# power.net
KiCad netlist of a schematic drawn in Altium Designer
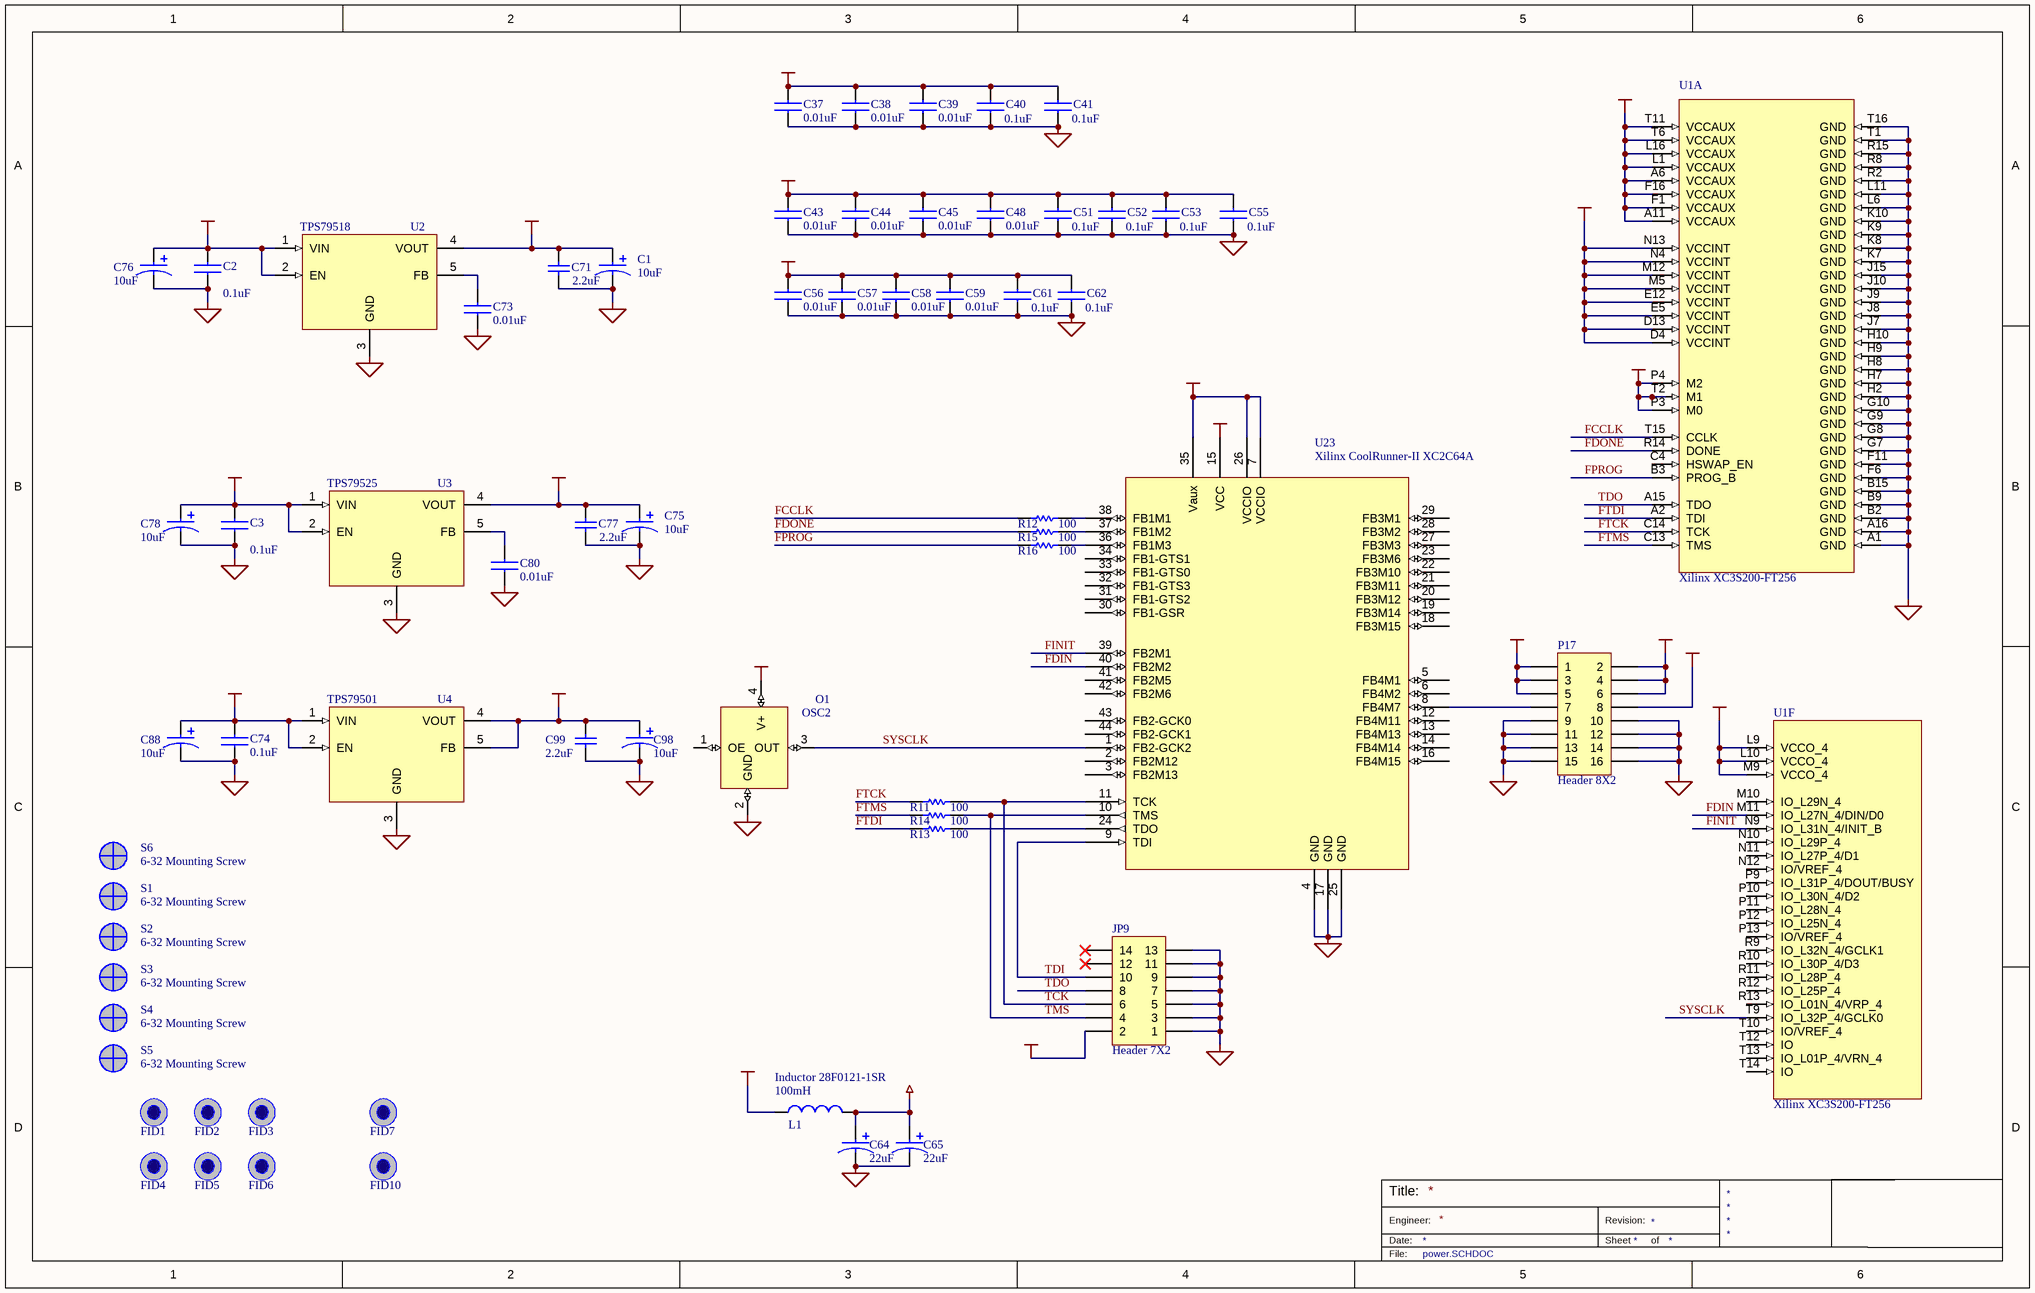
[diagram p0: power.SCHDOC]

(export (version "E")
  (design (tool "Eeschema 10.0.6"))
  (components
    (comp (ref "C1")
      (value "10uF")
      (footprint "6032")
      (description "Standard Capacitor")
      (fields (field (name "Comment") "POLCAP2"))
      (libsource (lib "parts") (part "POLCAP2"))
    )
    (comp (ref "C2")
      (value "0.1uF")
      (footprint "0603")
      (description "Standard Capacitor")
      (fields (field (name "Comment") "CAPACITOR"))
      (libsource (lib "parts") (part "CAPACITOR"))
    )
    (comp (ref "C3")
      (value "0.1uF")
      (footprint "0603")
      (description "Standard Capacitor")
      (fields (field (name "Comment") "CAPACITOR"))
      (libsource (lib "parts") (part "CAPACITOR"))
    )
    (comp (ref "C37")
      (value "0.01uF")
      (footprint "0402")
      (description "Standard Capacitor")
      (fields (field (name "Comment") "CAPACITOR"))
      (libsource (lib "parts") (part "CAPACITOR"))
    )
    (comp (ref "C38")
      (value "0.01uF")
      (footprint "0402")
      (description "Standard Capacitor")
      (fields (field (name "Comment") "CAPACITOR"))
      (libsource (lib "parts") (part "CAPACITOR"))
    )
    (comp (ref "C39")
      (value "0.01uF")
      (footprint "0402")
      (description "Standard Capacitor")
      (fields (field (name "Comment") "CAPACITOR"))
      (libsource (lib "parts") (part "CAPACITOR"))
    )
    (comp (ref "C40")
      (value "0.1uF")
      (footprint "0603")
      (description "Standard Capacitor")
      (fields (field (name "Comment") "CAPACITOR"))
      (libsource (lib "parts") (part "CAPACITOR"))
    )
    (comp (ref "C41")
      (value "0.1uF")
      (footprint "0603")
      (description "Standard Capacitor")
      (fields (field (name "Comment") "CAPACITOR"))
      (libsource (lib "parts") (part "CAPACITOR"))
    )
    (comp (ref "C43")
      (value "0.01uF")
      (footprint "0402")
      (description "Standard Capacitor")
      (fields (field (name "Comment") "CAPACITOR"))
      (libsource (lib "parts") (part "CAPACITOR"))
    )
    (comp (ref "C44")
      (value "0.01uF")
      (footprint "0402")
      (description "Standard Capacitor")
      (fields (field (name "Comment") "CAPACITOR"))
      (libsource (lib "parts") (part "CAPACITOR"))
    )
    (comp (ref "C45")
      (value "0.01uF")
      (footprint "0402")
      (description "Standard Capacitor")
      (fields (field (name "Comment") "CAPACITOR"))
      (libsource (lib "parts") (part "CAPACITOR"))
    )
    (comp (ref "C48")
      (value "0.01uF")
      (footprint "0402")
      (description "Standard Capacitor")
      (fields (field (name "Comment") "CAPACITOR"))
      (libsource (lib "parts") (part "CAPACITOR"))
    )
    (comp (ref "C51")
      (value "0.1uF")
      (footprint "0603")
      (description "Standard Capacitor")
      (fields (field (name "Comment") "CAPACITOR"))
      (libsource (lib "parts") (part "CAPACITOR"))
    )
    (comp (ref "C52")
      (value "0.1uF")
      (footprint "0603")
      (description "Standard Capacitor")
      (fields (field (name "Comment") "CAPACITOR"))
      (libsource (lib "parts") (part "CAPACITOR"))
    )
    (comp (ref "C53")
      (value "0.1uF")
      (footprint "0603")
      (description "Standard Capacitor")
      (fields (field (name "Comment") "CAPACITOR"))
      (libsource (lib "parts") (part "CAPACITOR"))
    )
    (comp (ref "C55")
      (value "0.1uF")
      (footprint "0603")
      (description "Standard Capacitor")
      (fields (field (name "Comment") "CAPACITOR"))
      (libsource (lib "parts") (part "CAPACITOR"))
    )
    (comp (ref "C56")
      (value "0.01uF")
      (footprint "0402")
      (description "Standard Capacitor")
      (fields (field (name "Comment") "CAPACITOR"))
      (libsource (lib "parts") (part "CAPACITOR"))
    )
    (comp (ref "C57")
      (value "0.01uF")
      (footprint "0402")
      (description "Standard Capacitor")
      (fields (field (name "Comment") "CAPACITOR"))
      (libsource (lib "parts") (part "CAPACITOR"))
    )
    (comp (ref "C58")
      (value "0.01uF")
      (footprint "0402")
      (description "Standard Capacitor")
      (fields (field (name "Comment") "CAPACITOR"))
      (libsource (lib "parts") (part "CAPACITOR"))
    )
    (comp (ref "C59")
      (value "0.01uF")
      (footprint "0402")
      (description "Standard Capacitor")
      (fields (field (name "Comment") "CAPACITOR"))
      (libsource (lib "parts") (part "CAPACITOR"))
    )
    (comp (ref "C61")
      (value "0.1uF")
      (footprint "0603")
      (description "Standard Capacitor")
      (fields (field (name "Comment") "CAPACITOR"))
      (libsource (lib "parts") (part "CAPACITOR"))
    )
    (comp (ref "C62")
      (value "0.1uF")
      (footprint "0603")
      (description "Standard Capacitor")
      (fields (field (name "Comment") "CAPACITOR"))
      (libsource (lib "parts") (part "CAPACITOR"))
    )
    (comp (ref "C64")
      (value "22uF")
      (footprint "6032")
      (description "Standard Capacitor")
      (fields (field (name "Comment") "POLCAP2"))
      (libsource (lib "parts") (part "POLCAP2"))
    )
    (comp (ref "C65")
      (value "22uF")
      (footprint "6032")
      (description "Standard Capacitor")
      (fields (field (name "Comment") "POLCAP2"))
      (libsource (lib "parts") (part "POLCAP2"))
    )
    (comp (ref "C71")
      (value "2.2uF")
      (footprint "1206")
      (description "Capacitor")
      (fields
        (field (name "MANUFACTURER") "Generic Components")
        (field (name "Comment") "Cap")
        (field (name "PUBLISHER") "Altium Limited")
      )
      (libsource (lib "Miscellaneous Devices") (part "Cap"))
    )
    (comp (ref "C73")
      (value "0.01uF")
      (footprint "0402")
      (description "Standard Capacitor")
      (fields (field (name "Comment") "CAPACITOR"))
      (libsource (lib "parts") (part "CAPACITOR"))
    )
    (comp (ref "C74")
      (value "0.1uF")
      (footprint "0603")
      (description "Standard Capacitor")
      (fields (field (name "Comment") "CAPACITOR"))
      (libsource (lib "parts") (part "CAPACITOR"))
    )
    (comp (ref "C75")
      (value "10uF")
      (footprint "6032")
      (description "Standard Capacitor")
      (fields (field (name "Comment") "POLCAP2"))
      (libsource (lib "parts") (part "POLCAP2"))
    )
    (comp (ref "C76")
      (value "10uF")
      (footprint "6032")
      (description "Standard Capacitor")
      (fields (field (name "Comment") "POLCAP2"))
      (libsource (lib "parts") (part "POLCAP2"))
    )
    (comp (ref "C77")
      (value "2.2uF")
      (footprint "1206")
      (description "Capacitor")
      (fields
        (field (name "MANUFACTURER") "Generic Components")
        (field (name "Comment") "Cap")
        (field (name "PUBLISHER") "Altium Limited")
      )
      (libsource (lib "Miscellaneous Devices") (part "Cap"))
    )
    (comp (ref "C78")
      (value "10uF")
      (footprint "6032")
      (description "Standard Capacitor")
      (fields (field (name "Comment") "POLCAP2"))
      (libsource (lib "parts") (part "POLCAP2"))
    )
    (comp (ref "C80")
      (value "0.01uF")
      (footprint "0402")
      (description "Standard Capacitor")
      (fields (field (name "Comment") "CAPACITOR"))
      (libsource (lib "parts") (part "CAPACITOR"))
    )
    (comp (ref "C88")
      (value "10uF")
      (footprint "6032")
      (description "Standard Capacitor")
      (fields (field (name "Comment") "POLCAP2"))
      (libsource (lib "parts") (part "POLCAP2"))
    )
    (comp (ref "C98")
      (value "10uF")
      (footprint "6032")
      (description "Standard Capacitor")
      (fields (field (name "Comment") "POLCAP2"))
      (libsource (lib "parts") (part "POLCAP2"))
    )
    (comp (ref "C99")
      (value "2.2uF")
      (footprint "1206")
      (description "Capacitor")
      (fields
        (field (name "MANUFACTURER") "Generic Components")
        (field (name "Comment") "Cap")
        (field (name "PUBLISHER") "Altium Limited")
      )
      (libsource (lib "Miscellaneous Devices") (part "Cap"))
    )
    (comp (ref "FID1")
      (value "FIDUCIAL")
      (footprint "FIDUCIAL")
      (description "Fiducial")
      (libsource (lib "parts") (part "FIDUCIAL"))
    )
    (comp (ref "FID2")
      (value "FIDUCIAL")
      (footprint "FIDUCIAL")
      (description "Fiducial")
      (libsource (lib "parts") (part "FIDUCIAL"))
    )
    (comp (ref "FID3")
      (value "FIDUCIAL")
      (footprint "FIDUCIAL")
      (description "Fiducial")
      (libsource (lib "parts") (part "FIDUCIAL"))
    )
    (comp (ref "FID4")
      (value "FIDUCIAL")
      (footprint "FIDUCIAL")
      (description "Fiducial")
      (libsource (lib "parts") (part "FIDUCIAL"))
    )
    (comp (ref "FID5")
      (value "FIDUCIAL")
      (footprint "FIDUCIAL")
      (description "Fiducial")
      (libsource (lib "parts") (part "FIDUCIAL"))
    )
    (comp (ref "FID6")
      (value "FIDUCIAL")
      (footprint "FIDUCIAL")
      (description "Fiducial")
      (libsource (lib "parts") (part "FIDUCIAL"))
    )
    (comp (ref "FID7")
      (value "FIDUCIAL")
      (footprint "FIDUCIAL")
      (description "Fiducial")
      (libsource (lib "parts") (part "FIDUCIAL"))
    )
    (comp (ref "FID10")
      (value "FIDUCIAL")
      (footprint "FIDUCIAL")
      (description "Fiducial")
      (libsource (lib "parts") (part "FIDUCIAL"))
    )
    (comp (ref "JP9")
      (value "Header 7X2")
      (footprint "SMT 2x7 2mm HDR")
      (description "Header, 7-Pin, Dual row")
      (fields (field (name "MANUFACTURER") "Generic Components") (field (name "PUBLISHER") "Altium Limited"))
      (libsource (lib "Miscellaneous Connectors") (part "Header 7X2"))
    )
    (comp (ref "L1")
      (value "Inductor 28F0121-1SR")
      (footprint "STEWARD_1SR")
      (description "Inductor")
      (fields
        (field (name "MANUFACTURER") "Generic Components")
        (field (name "ALTIUM_VALUE") "100mH")
        (field (name "PUBLISHER") "Altium Limited")
      )
      (libsource (lib "Miscellaneous Devices") (part "Inductor"))
    )
    (comp (ref "O1")
      (value "OSC2")
      (footprint "ECS-3953M")
      (description "ECS SMD Oscillator, ECS-3953M")
      (libsource (lib "parts") (part "OSC2"))
    )
    (comp (ref "P17")
      (value "Header 8X2")
      (footprint "MOLEX 15-91-2160")
      (description "Header, 8-Pin, Dual row")
      (fields (field (name "PUBLISHER") "Altium Limited"))
      (libsource (lib "Miscellaneous Connectors") (part "Header 8X2"))
    )
    (comp (ref "R11")
      (value "100")
      (footprint "0603")
      (description "Standard Passive Resistor")
      (fields (field (name "TOLERANCE") "1%") (field (name "Comment") "current-limiting series res"))
      (libsource (lib "parts") (part "RESISTOR"))
    )
    (comp (ref "R12")
      (value "100")
      (footprint "0603")
      (description "Standard Passive Resistor")
      (fields (field (name "TOLERANCE") "1%") (field (name "Comment") "current-limiting series res"))
      (libsource (lib "parts") (part "RESISTOR"))
    )
    (comp (ref "R13")
      (value "100")
      (footprint "0603")
      (description "Standard Passive Resistor")
      (fields (field (name "TOLERANCE") "1%") (field (name "Comment") "current-limiting series res"))
      (libsource (lib "parts") (part "RESISTOR"))
    )
    (comp (ref "R14")
      (value "100")
      (footprint "0603")
      (description "Standard Passive Resistor")
      (fields (field (name "TOLERANCE") "1%") (field (name "Comment") "current-limiting series res"))
      (libsource (lib "parts") (part "RESISTOR"))
    )
    (comp (ref "R15")
      (value "100")
      (footprint "0603")
      (description "Standard Passive Resistor")
      (fields (field (name "TOLERANCE") "1%") (field (name "Comment") "current-limiting series res"))
      (libsource (lib "parts") (part "RESISTOR"))
    )
    (comp (ref "R16")
      (value "100")
      (footprint "0603")
      (description "Standard Passive Resistor")
      (fields (field (name "TOLERANCE") "1%") (field (name "Comment") "current-limiting series res"))
      (libsource (lib "parts") (part "RESISTOR"))
    )
    (comp (ref "S1")
      (value "6-32 Mounting Screw")
      (footprint "SCREW6-32")
      (libsource (lib "parts") (part "MNTSCREW"))
    )
    (comp (ref "S2")
      (value "6-32 Mounting Screw")
      (footprint "SCREW6-32")
      (libsource (lib "parts") (part "MNTSCREW"))
    )
    (comp (ref "S3")
      (value "6-32 Mounting Screw")
      (footprint "SCREW6-32")
      (libsource (lib "parts") (part "MNTSCREW"))
    )
    (comp (ref "S4")
      (value "6-32 Mounting Screw")
      (footprint "SCREW6-32")
      (libsource (lib "parts") (part "MNTSCREW"))
    )
    (comp (ref "S5")
      (value "6-32 Mounting Screw")
      (footprint "SCREW6-32")
      (libsource (lib "parts") (part "MNTSCREW"))
    )
    (comp (ref "S6")
      (value "6-32 Mounting Screw")
      (footprint "SCREW6-32")
      (libsource (lib "parts") (part "MNTSCREW"))
    )
    (comp (ref "U1")
      (value "Xilinx XC3S200-FT256")
      (footprint "Xilinx FT256 BGA")
      (description "Xilinx Spartan-3 FPGA")
      (libsource (lib "parts") (part "XC3S200-FT256"))
    )
    (comp (ref "U2")
      (value "TPS79518")
      (footprint "SOT223-5/Simple")
      (description "TI Ultra-low-noise LDO")
      (libsource (lib "parts") (part "TPS795XX"))
    )
    (comp (ref "U3")
      (value "TPS79525")
      (footprint "SOT223-5/Simple")
      (description "TI Ultra-low-noise LDO")
      (libsource (lib "parts") (part "TPS795XX"))
    )
    (comp (ref "U4")
      (value "TPS79501")
      (footprint "SOT223-5/Simple")
      (description "TI Ultra-low-noise LDO")
      (libsource (lib "parts") (part "TPS795XX"))
    )
    (comp (ref "U23")
      (value "Xilinx CoolRunner-II XC2C64A")
      (footprint "QFP10x10-G44/G10N")
      (libsource (lib "parts") (part "XC2C64A-5VQ44C"))
    )
  )
  (nets
    (net (code "1") (name "+1.2VCC") (class "Default")
      (node (ref "C37") (pin "1") (pintype "passive"))
      (node (ref "C38") (pin "1") (pintype "passive"))
      (node (ref "C39") (pin "1") (pintype "passive"))
      (node (ref "C40") (pin "1") (pintype "passive"))
      (node (ref "C41") (pin "1") (pintype "passive"))
      (node (ref "C98") (pin "1") (pintype "passive"))
      (node (ref "C99") (pin "2") (pinfunction "2_2") (pintype "passive"))
      (node (ref "U1") (pin "D13") (pinfunction "VCCINT_D13") (pintype "input"))
      (node (ref "U1") (pin "D4") (pinfunction "VCCINT_D4") (pintype "input"))
      (node (ref "U1") (pin "E12") (pinfunction "VCCINT_E12") (pintype "input"))
      (node (ref "U1") (pin "E5") (pinfunction "VCCINT_E5") (pintype "input"))
      (node (ref "U1") (pin "M12") (pinfunction "VCCINT_M12") (pintype "input"))
      (node (ref "U1") (pin "M5") (pinfunction "VCCINT_M5") (pintype "input"))
      (node (ref "U1") (pin "N13") (pinfunction "VCCINT_N13") (pintype "input"))
      (node (ref "U1") (pin "N4") (pinfunction "VCCINT_N4") (pintype "input"))
      (node (ref "U4") (pin "4") (pinfunction "VOUT_4") (pintype "power_in"))
      (node (ref "U4") (pin "5") (pinfunction "FB_5") (pintype "passive"))
    )
    (net (code "2") (name "+1.8VCC") (class "Default")
      (node (ref "C1") (pin "1") (pintype "passive"))
      (node (ref "C71") (pin "2") (pinfunction "2_2") (pintype "passive"))
      (node (ref "U2") (pin "4") (pinfunction "VOUT_4") (pintype "power_in"))
      (node (ref "U23") (pin "15") (pinfunction "VCC_15") (pintype "power_in"))
    )
    (net (code "3") (name "+2.5VCC") (class "Default")
      (node (ref "C43") (pin "1") (pintype "passive"))
      (node (ref "C44") (pin "1") (pintype "passive"))
      (node (ref "C45") (pin "1") (pintype "passive"))
      (node (ref "C48") (pin "1") (pintype "passive"))
      (node (ref "C51") (pin "1") (pintype "passive"))
      (node (ref "C52") (pin "1") (pintype "passive"))
      (node (ref "C53") (pin "1") (pintype "passive"))
      (node (ref "C55") (pin "1") (pintype "passive"))
      (node (ref "C75") (pin "1") (pintype "passive"))
      (node (ref "C77") (pin "2") (pinfunction "2_2") (pintype "passive"))
      (node (ref "U1") (pin "A11") (pinfunction "VCCAUX_A11") (pintype "input"))
      (node (ref "U1") (pin "A6") (pinfunction "VCCAUX_A6") (pintype "input"))
      (node (ref "U1") (pin "F1") (pinfunction "VCCAUX_F1") (pintype "input"))
      (node (ref "U1") (pin "F16") (pinfunction "VCCAUX_F16") (pintype "input"))
      (node (ref "U1") (pin "L1") (pinfunction "VCCAUX_L1") (pintype "input"))
      (node (ref "U1") (pin "L16") (pinfunction "VCCAUX_L16") (pintype "input"))
      (node (ref "U1") (pin "T11") (pinfunction "VCCAUX_T11") (pintype "input"))
      (node (ref "U1") (pin "T6") (pinfunction "VCCAUX_T6") (pintype "input"))
      (node (ref "U3") (pin "4") (pinfunction "VOUT_4") (pintype "power_in"))
    )
    (net (code "4") (name "+5VCC") (class "Default")
      (node (ref "L1") (pin "1") (pinfunction "1_1") (pintype "passive"))
      (node (ref "P17") (pin "2") (pinfunction "2_2") (pintype "passive"))
      (node (ref "P17") (pin "4") (pinfunction "4_4") (pintype "passive"))
      (node (ref "P17") (pin "6") (pinfunction "6_6") (pintype "passive"))
    )
    (net (code "5") (name "+12VCC") (class "Default")
      (node (ref "P17") (pin "8") (pinfunction "8_8") (pintype "passive"))
    )
    (net (code "6") (name "/FCCLK") (class "Default")
      (node (ref "R12") (pin "2") (pintype "passive"))
      (node (ref "U1") (pin "T15") (pinfunction "CCLK_T15") (pintype "input"))
    )
    (net (code "7") (name "/FDIN") (class "Default")
      (node (ref "U1") (pin "M11") (pinfunction "IO_L27N_4/DIN/D0_M11") (pintype "input"))
      (node (ref "U23") (pin "40") (pinfunction "FB2M2_40") (pintype "bidirectional"))
    )
    (net (code "8") (name "/FDONE") (class "Default")
      (node (ref "R15") (pin "2") (pintype "passive"))
      (node (ref "U1") (pin "R14") (pinfunction "DONE_R14") (pintype "input"))
    )
    (net (code "9") (name "/FINIT") (class "Default")
      (node (ref "U1") (pin "N9") (pinfunction "IO_L31N_4/INIT_B_N9") (pintype "input"))
      (node (ref "U23") (pin "39") (pinfunction "FB2M1_39") (pintype "bidirectional"))
    )
    (net (code "10") (name "/FPROG") (class "Default")
      (node (ref "R16") (pin "2") (pintype "passive"))
      (node (ref "U1") (pin "B3") (pinfunction "PROG_B_B3") (pintype "input"))
    )
    (net (code "11") (name "/FTCK") (class "Default")
      (node (ref "R11") (pin "2") (pintype "passive"))
      (node (ref "U1") (pin "C14") (pinfunction "TCK_C14") (pintype "input"))
    )
    (net (code "12") (name "/FTDI") (class "Default")
      (node (ref "R13") (pin "2") (pintype "passive"))
      (node (ref "U1") (pin "A2") (pinfunction "TDI_A2") (pintype "input"))
    )
    (net (code "13") (name "/FTMS") (class "Default")
      (node (ref "R14") (pin "1") (pintype "passive"))
      (node (ref "U1") (pin "C13") (pinfunction "TMS_C13") (pintype "input"))
    )
    (net (code "14") (name "/SYSCLK") (class "Default")
      (node (ref "O1") (pin "3") (pinfunction "OUT_3") (pintype "bidirectional"))
      (node (ref "U1") (pin "T9") (pinfunction "IO_L32P_4/GCLK0_T9") (pintype "input"))
      (node (ref "U23") (pin "1") (pinfunction "FB2-GCK2_1") (pintype "bidirectional"))
    )
    (net (code "15") (name "/TCK") (class "Default")
      (node (ref "JP9") (pin "6") (pinfunction "6_6") (pintype "passive"))
      (node (ref "R11") (pin "1") (pintype "passive"))
      (node (ref "U23") (pin "11") (pinfunction "TCK_11") (pintype "input"))
    )
    (net (code "16") (name "/TDI") (class "Default")
      (node (ref "JP9") (pin "10") (pinfunction "10_10") (pintype "passive"))
      (node (ref "U23") (pin "9") (pinfunction "TDI_9") (pintype "input"))
    )
    (net (code "17") (name "/TDO") (class "Default")
      (node (ref "JP9") (pin "8") (pinfunction "8_8") (pintype "passive"))
      (node (ref "U1") (pin "A15") (pinfunction "TDO_A15") (pintype "input"))
    )
    (net (code "18") (name "/TMS") (class "Default")
      (node (ref "JP9") (pin "4") (pinfunction "4_4") (pintype "passive"))
      (node (ref "R14") (pin "2") (pintype "passive"))
      (node (ref "U23") (pin "10") (pinfunction "TMS_10") (pintype "output"))
    )
    (net (code "19") (name "AVDD") (class "Default")
      (node (ref "C64") (pin "1") (pintype "passive"))
      (node (ref "C65") (pin "1") (pintype "passive"))
      (node (ref "L1") (pin "2") (pinfunction "2_2") (pintype "passive"))
    )
    (net (code "20") (name "GND") (class "Default")
      (node (ref "C1") (pin "2") (pintype "passive"))
      (node (ref "C2") (pin "1") (pintype "passive"))
      (node (ref "C3") (pin "1") (pintype "passive"))
      (node (ref "C37") (pin "2") (pintype "passive"))
      (node (ref "C38") (pin "2") (pintype "passive"))
      (node (ref "C39") (pin "2") (pintype "passive"))
      (node (ref "C40") (pin "2") (pintype "passive"))
      (node (ref "C41") (pin "2") (pintype "passive"))
      (node (ref "C43") (pin "2") (pintype "passive"))
      (node (ref "C44") (pin "2") (pintype "passive"))
      (node (ref "C45") (pin "2") (pintype "passive"))
      (node (ref "C48") (pin "2") (pintype "passive"))
      (node (ref "C51") (pin "2") (pintype "passive"))
      (node (ref "C52") (pin "2") (pintype "passive"))
      (node (ref "C53") (pin "2") (pintype "passive"))
      (node (ref "C55") (pin "2") (pintype "passive"))
      (node (ref "C56") (pin "2") (pintype "passive"))
      (node (ref "C57") (pin "2") (pintype "passive"))
      (node (ref "C58") (pin "2") (pintype "passive"))
      (node (ref "C59") (pin "2") (pintype "passive"))
      (node (ref "C61") (pin "2") (pintype "passive"))
      (node (ref "C62") (pin "2") (pintype "passive"))
      (node (ref "C64") (pin "2") (pintype "passive"))
      (node (ref "C65") (pin "2") (pintype "passive"))
      (node (ref "C71") (pin "1") (pinfunction "1_1") (pintype "passive"))
      (node (ref "C73") (pin "1") (pintype "passive"))
      (node (ref "C74") (pin "1") (pintype "passive"))
      (node (ref "C75") (pin "2") (pintype "passive"))
      (node (ref "C76") (pin "2") (pintype "passive"))
      (node (ref "C77") (pin "1") (pinfunction "1_1") (pintype "passive"))
      (node (ref "C78") (pin "2") (pintype "passive"))
      (node (ref "C80") (pin "1") (pintype "passive"))
      (node (ref "C88") (pin "2") (pintype "passive"))
      (node (ref "C98") (pin "2") (pintype "passive"))
      (node (ref "C99") (pin "1") (pinfunction "1_1") (pintype "passive"))
      (node (ref "JP9") (pin "1") (pinfunction "1_1") (pintype "passive"))
      (node (ref "JP9") (pin "11") (pinfunction "11_11") (pintype "passive"))
      (node (ref "JP9") (pin "13") (pinfunction "13_13") (pintype "passive"))
      (node (ref "JP9") (pin "3") (pinfunction "3_3") (pintype "passive"))
      (node (ref "JP9") (pin "5") (pinfunction "5_5") (pintype "passive"))
      (node (ref "JP9") (pin "7") (pinfunction "7_7") (pintype "passive"))
      (node (ref "JP9") (pin "9") (pinfunction "9_9") (pintype "passive"))
      (node (ref "O1") (pin "2") (pinfunction "GND_2") (pintype "bidirectional"))
      (node (ref "P17") (pin "10") (pinfunction "10_10") (pintype "passive"))
      (node (ref "P17") (pin "11") (pinfunction "11_11") (pintype "passive"))
      (node (ref "P17") (pin "12") (pinfunction "12_12") (pintype "passive"))
      (node (ref "P17") (pin "13") (pinfunction "13_13") (pintype "passive"))
      (node (ref "P17") (pin "14") (pinfunction "14_14") (pintype "passive"))
      (node (ref "P17") (pin "15") (pinfunction "15_15") (pintype "passive"))
      (node (ref "P17") (pin "16") (pinfunction "16_16") (pintype "passive"))
      (node (ref "P17") (pin "9") (pinfunction "9_9") (pintype "passive"))
      (node (ref "U1") (pin "A1") (pinfunction "GND_A1") (pintype "input"))
      (node (ref "U1") (pin "A16") (pinfunction "GND_A16") (pintype "input"))
      (node (ref "U1") (pin "B15") (pinfunction "GND_B15") (pintype "input"))
      (node (ref "U1") (pin "B2") (pinfunction "GND_B2") (pintype "input"))
      (node (ref "U1") (pin "B9") (pinfunction "GND_B9") (pintype "input"))
      (node (ref "U1") (pin "F11") (pinfunction "GND_F11") (pintype "input"))
      (node (ref "U1") (pin "F6") (pinfunction "GND_F6") (pintype "input"))
      (node (ref "U1") (pin "G10") (pinfunction "GND_G10") (pintype "input"))
      (node (ref "U1") (pin "G7") (pinfunction "GND_G7") (pintype "input"))
      (node (ref "U1") (pin "G8") (pinfunction "GND_G8") (pintype "input"))
      (node (ref "U1") (pin "G9") (pinfunction "GND_G9") (pintype "input"))
      (node (ref "U1") (pin "H10") (pinfunction "GND_H10") (pintype "input"))
      (node (ref "U1") (pin "H2") (pinfunction "GND_H2") (pintype "input"))
      (node (ref "U1") (pin "H7") (pinfunction "GND_H7") (pintype "input"))
      (node (ref "U1") (pin "H8") (pinfunction "GND_H8") (pintype "input"))
      (node (ref "U1") (pin "H9") (pinfunction "GND_H9") (pintype "input"))
      (node (ref "U1") (pin "J10") (pinfunction "GND_J10") (pintype "input"))
      (node (ref "U1") (pin "J15") (pinfunction "GND_J15") (pintype "input"))
      (node (ref "U1") (pin "J7") (pinfunction "GND_J7") (pintype "input"))
      (node (ref "U1") (pin "J8") (pinfunction "GND_J8") (pintype "input"))
      (node (ref "U1") (pin "J9") (pinfunction "GND_J9") (pintype "input"))
      (node (ref "U1") (pin "K10") (pinfunction "GND_K10") (pintype "input"))
      (node (ref "U1") (pin "K7") (pinfunction "GND_K7") (pintype "input"))
      (node (ref "U1") (pin "K8") (pinfunction "GND_K8") (pintype "input"))
      (node (ref "U1") (pin "K9") (pinfunction "GND_K9") (pintype "input"))
      (node (ref "U1") (pin "L11") (pinfunction "GND_L11") (pintype "input"))
      (node (ref "U1") (pin "L6") (pinfunction "GND_L6") (pintype "input"))
      (node (ref "U1") (pin "R15") (pinfunction "GND_R15") (pintype "input"))
      (node (ref "U1") (pin "R2") (pinfunction "GND_R2") (pintype "input"))
      (node (ref "U1") (pin "R8") (pinfunction "GND_R8") (pintype "input"))
      (node (ref "U1") (pin "T1") (pinfunction "GND_T1") (pintype "input"))
      (node (ref "U1") (pin "T16") (pinfunction "GND_T16") (pintype "input"))
      (node (ref "U2") (pin "3") (pinfunction "GND_3") (pintype "power_in"))
      (node (ref "U23") (pin "17") (pinfunction "GND_17") (pintype "power_in"))
      (node (ref "U23") (pin "25") (pinfunction "GND_25") (pintype "power_in"))
      (node (ref "U23") (pin "4") (pinfunction "GND_4") (pintype "power_in"))
      (node (ref "U3") (pin "3") (pinfunction "GND_3") (pintype "power_in"))
      (node (ref "U4") (pin "3") (pinfunction "GND_3") (pintype "power_in"))
    )
    (net (code "21") (name "Net-(U2-FB)") (class "Default")
      (node (ref "C73") (pin "2") (pintype "passive"))
      (node (ref "U2") (pin "5") (pinfunction "FB_5") (pintype "passive"))
    )
    (net (code "22") (name "Net-(U3-FB)") (class "Default")
      (node (ref "C80") (pin "2") (pintype "passive"))
      (node (ref "U3") (pin "5") (pinfunction "FB_5") (pintype "passive"))
    )
    (net (code "23") (name "Net-(U23-FB1M1)") (class "Default")
      (node (ref "R12") (pin "1") (pintype "passive"))
      (node (ref "U23") (pin "38") (pinfunction "FB1M1_38") (pintype "bidirectional"))
    )
    (net (code "24") (name "Net-(U23-FB1M2)") (class "Default")
      (node (ref "R15") (pin "1") (pintype "passive"))
      (node (ref "U23") (pin "37") (pinfunction "FB1M2_37") (pintype "bidirectional"))
    )
    (net (code "25") (name "Net-(U23-FB1M3)") (class "Default")
      (node (ref "R16") (pin "1") (pintype "passive"))
      (node (ref "U23") (pin "36") (pinfunction "FB1M3_36") (pintype "bidirectional"))
    )
    (net (code "26") (name "Net-(U23-FB4M7)") (class "Default")
      (node (ref "P17") (pin "7") (pinfunction "7_7") (pintype "passive"))
      (node (ref "U23") (pin "8") (pinfunction "FB4M7_8") (pintype "bidirectional"))
    )
    (net (code "27") (name "Net-(U23-TDO)") (class "Default")
      (node (ref "R13") (pin "1") (pintype "passive"))
      (node (ref "U23") (pin "24") (pinfunction "TDO_24") (pintype "output"))
    )
    (net (code "28") (name "VCC") (class "Default")
      (node (ref "C2") (pin "2") (pintype "passive"))
      (node (ref "C3") (pin "2") (pintype "passive"))
      (node (ref "C56") (pin "1") (pintype "passive"))
      (node (ref "C57") (pin "1") (pintype "passive"))
      (node (ref "C58") (pin "1") (pintype "passive"))
      (node (ref "C59") (pin "1") (pintype "passive"))
      (node (ref "C61") (pin "1") (pintype "passive"))
      (node (ref "C62") (pin "1") (pintype "passive"))
      (node (ref "C74") (pin "2") (pintype "passive"))
      (node (ref "C76") (pin "1") (pintype "passive"))
      (node (ref "C78") (pin "1") (pintype "passive"))
      (node (ref "C88") (pin "1") (pintype "passive"))
      (node (ref "JP9") (pin "2") (pinfunction "2_2") (pintype "passive"))
      (node (ref "O1") (pin "4") (pinfunction "V+_4") (pintype "bidirectional"))
      (node (ref "P17") (pin "1") (pinfunction "1_1") (pintype "passive"))
      (node (ref "P17") (pin "3") (pinfunction "3_3") (pintype "passive"))
      (node (ref "P17") (pin "5") (pinfunction "5_5") (pintype "passive"))
      (node (ref "U1") (pin "L10") (pinfunction "VCCO_4_L10") (pintype "input"))
      (node (ref "U1") (pin "L9") (pinfunction "VCCO_4_L9") (pintype "input"))
      (node (ref "U1") (pin "M9") (pinfunction "VCCO_4_M9") (pintype "input"))
      (node (ref "U1") (pin "P3") (pinfunction "M0_P3") (pintype "input"))
      (node (ref "U1") (pin "P4") (pinfunction "M2_P4") (pintype "input"))
      (node (ref "U1") (pin "T2") (pinfunction "M1_T2") (pintype "input"))
      (node (ref "U2") (pin "1") (pinfunction "VIN_1") (pintype "input"))
      (node (ref "U2") (pin "2") (pinfunction "EN_2") (pintype "input"))
      (node (ref "U23") (pin "26") (pinfunction "VCCIO_26") (pintype "power_in"))
      (node (ref "U23") (pin "35") (pinfunction "Vaux_35") (pintype "power_in"))
      (node (ref "U23") (pin "7") (pinfunction "VCCIO_7") (pintype "power_in"))
      (node (ref "U3") (pin "1") (pinfunction "VIN_1") (pintype "input"))
      (node (ref "U3") (pin "2") (pinfunction "EN_2") (pintype "input"))
      (node (ref "U4") (pin "1") (pinfunction "VIN_1") (pintype "input"))
      (node (ref "U4") (pin "2") (pinfunction "EN_2") (pintype "input"))
    )
    (net (code "29") (name "unconnected-(JP9-Pad12)") (class "Default")
      (node (ref "JP9") (pin "12") (pinfunction "12_12") (pintype "passive+no_connect"))
    )
    (net (code "30") (name "unconnected-(JP9-Pad14)") (class "Default")
      (node (ref "JP9") (pin "14") (pinfunction "14_14") (pintype "passive+no_connect"))
    )
    (net (code "31") (name "unconnected-(O1-OE-Pad1)") (class "Default")
      (node (ref "O1") (pin "1") (pinfunction "OE_1") (pintype "bidirectional"))
    )
    (net (code "32") (name "unconnected-(U1A-HSWAP_EN-PadC4)") (class "Default")
      (node (ref "U1") (pin "C4") (pinfunction "HSWAP_EN_C4") (pintype "input"))
    )
    (net (code "33") (name "unconnected-(U1F-IO-PadT12)") (class "Default")
      (node (ref "U1") (pin "T12") (pinfunction "IO_T12") (pintype "input"))
    )
    (net (code "34") (name "unconnected-(U1F-IO-PadT14)") (class "Default")
      (node (ref "U1") (pin "T14") (pinfunction "IO_T14") (pintype "input"))
    )
    (net (code "35") (name "unconnected-(U1F-IO_L01N_4{slash}VRP_4-PadR13)") (class "Default")
      (node (ref "U1") (pin "R13") (pinfunction "IO_L01N_4/VRP_4_R13") (pintype "input"))
    )
    (net (code "36") (name "unconnected-(U1F-IO_L01P_4{slash}VRN_4-PadT13)") (class "Default")
      (node (ref "U1") (pin "T13") (pinfunction "IO_L01P_4/VRN_4_T13") (pintype "input"))
    )
    (net (code "37") (name "unconnected-(U1F-IO_L25N_4-PadP12)") (class "Default")
      (node (ref "U1") (pin "P12") (pinfunction "IO_L25N_4_P12") (pintype "input"))
    )
    (net (code "38") (name "unconnected-(U1F-IO_L25P_4-PadR12)") (class "Default")
      (node (ref "U1") (pin "R12") (pinfunction "IO_L25P_4_R12") (pintype "input"))
    )
    (net (code "39") (name "unconnected-(U1F-IO_L27P_4{slash}D1-PadN11)") (class "Default")
      (node (ref "U1") (pin "N11") (pinfunction "IO_L27P_4/D1_N11") (pintype "input"))
    )
    (net (code "40") (name "unconnected-(U1F-IO_L28N_4-PadP11)") (class "Default")
      (node (ref "U1") (pin "P11") (pinfunction "IO_L28N_4_P11") (pintype "input"))
    )
    (net (code "41") (name "unconnected-(U1F-IO_L28P_4-PadR11)") (class "Default")
      (node (ref "U1") (pin "R11") (pinfunction "IO_L28P_4_R11") (pintype "input"))
    )
    (net (code "42") (name "unconnected-(U1F-IO_L29N_4-PadM10)") (class "Default")
      (node (ref "U1") (pin "M10") (pinfunction "IO_L29N_4_M10") (pintype "input"))
    )
    (net (code "43") (name "unconnected-(U1F-IO_L29P_4-PadN10)") (class "Default")
      (node (ref "U1") (pin "N10") (pinfunction "IO_L29P_4_N10") (pintype "input"))
    )
    (net (code "44") (name "unconnected-(U1F-IO_L30N_4{slash}D2-PadP10)") (class "Default")
      (node (ref "U1") (pin "P10") (pinfunction "IO_L30N_4/D2_P10") (pintype "input"))
    )
    (net (code "45") (name "unconnected-(U1F-IO_L30P_4{slash}D3-PadR10)") (class "Default")
      (node (ref "U1") (pin "R10") (pinfunction "IO_L30P_4/D3_R10") (pintype "input"))
    )
    (net (code "46") (name "unconnected-(U1F-IO_L31P_4{slash}DOUT{slash}BUSY-PadP9)") (class "Default")
      (node (ref "U1") (pin "P9") (pinfunction "IO_L31P_4/DOUT/BUSY_P9") (pintype "input"))
    )
    (net (code "47") (name "unconnected-(U1F-IO_L32N_4{slash}GCLK1-PadR9)") (class "Default")
      (node (ref "U1") (pin "R9") (pinfunction "IO_L32N_4/GCLK1_R9") (pintype "input"))
    )
    (net (code "48") (name "unconnected-(U1F-IO{slash}VREF_4-PadN12)") (class "Default")
      (node (ref "U1") (pin "N12") (pinfunction "IO/VREF_4_N12") (pintype "input"))
    )
    (net (code "49") (name "unconnected-(U1F-IO{slash}VREF_4-PadP13)") (class "Default")
      (node (ref "U1") (pin "P13") (pinfunction "IO/VREF_4_P13") (pintype "input"))
    )
    (net (code "50") (name "unconnected-(U1F-IO{slash}VREF_4-PadT10)") (class "Default")
      (node (ref "U1") (pin "T10") (pinfunction "IO/VREF_4_T10") (pintype "input"))
    )
    (net (code "51") (name "unconnected-(U23-FB1-GSR-Pad30)") (class "Default")
      (node (ref "U23") (pin "30") (pinfunction "FB1-GSR_30") (pintype "bidirectional"))
    )
    (net (code "52") (name "unconnected-(U23-FB1-GTS0-Pad33)") (class "Default")
      (node (ref "U23") (pin "33") (pinfunction "FB1-GTS0_33") (pintype "bidirectional"))
    )
    (net (code "53") (name "unconnected-(U23-FB1-GTS1-Pad34)") (class "Default")
      (node (ref "U23") (pin "34") (pinfunction "FB1-GTS1_34") (pintype "bidirectional"))
    )
    (net (code "54") (name "unconnected-(U23-FB1-GTS2-Pad31)") (class "Default")
      (node (ref "U23") (pin "31") (pinfunction "FB1-GTS2_31") (pintype "bidirectional"))
    )
    (net (code "55") (name "unconnected-(U23-FB1-GTS3-Pad32)") (class "Default")
      (node (ref "U23") (pin "32") (pinfunction "FB1-GTS3_32") (pintype "bidirectional"))
    )
    (net (code "56") (name "unconnected-(U23-FB2-GCK0-Pad43)") (class "Default")
      (node (ref "U23") (pin "43") (pinfunction "FB2-GCK0_43") (pintype "bidirectional"))
    )
    (net (code "57") (name "unconnected-(U23-FB2-GCK1-Pad44)") (class "Default")
      (node (ref "U23") (pin "44") (pinfunction "FB2-GCK1_44") (pintype "bidirectional"))
    )
    (net (code "58") (name "unconnected-(U23-FB2M5-Pad41)") (class "Default")
      (node (ref "U23") (pin "41") (pinfunction "FB2M5_41") (pintype "bidirectional"))
    )
    (net (code "59") (name "unconnected-(U23-FB2M6-Pad42)") (class "Default")
      (node (ref "U23") (pin "42") (pinfunction "FB2M6_42") (pintype "bidirectional"))
    )
    (net (code "60") (name "unconnected-(U23-FB2M12-Pad2)") (class "Default")
      (node (ref "U23") (pin "2") (pinfunction "FB2M12_2") (pintype "bidirectional"))
    )
    (net (code "61") (name "unconnected-(U23-FB2M13-Pad3)") (class "Default")
      (node (ref "U23") (pin "3") (pinfunction "FB2M13_3") (pintype "bidirectional"))
    )
    (net (code "62") (name "unconnected-(U23-FB3M1-Pad29)") (class "Default")
      (node (ref "U23") (pin "29") (pinfunction "FB3M1_29") (pintype "bidirectional"))
    )
    (net (code "63") (name "unconnected-(U23-FB3M2-Pad28)") (class "Default")
      (node (ref "U23") (pin "28") (pinfunction "FB3M2_28") (pintype "bidirectional"))
    )
    (net (code "64") (name "unconnected-(U23-FB3M3-Pad27)") (class "Default")
      (node (ref "U23") (pin "27") (pinfunction "FB3M3_27") (pintype "bidirectional"))
    )
    (net (code "65") (name "unconnected-(U23-FB3M6-Pad23)") (class "Default")
      (node (ref "U23") (pin "23") (pinfunction "FB3M6_23") (pintype "bidirectional"))
    )
    (net (code "66") (name "unconnected-(U23-FB3M10-Pad22)") (class "Default")
      (node (ref "U23") (pin "22") (pinfunction "FB3M10_22") (pintype "bidirectional"))
    )
    (net (code "67") (name "unconnected-(U23-FB3M11-Pad21)") (class "Default")
      (node (ref "U23") (pin "21") (pinfunction "FB3M11_21") (pintype "bidirectional"))
    )
    (net (code "68") (name "unconnected-(U23-FB3M12-Pad20)") (class "Default")
      (node (ref "U23") (pin "20") (pinfunction "FB3M12_20") (pintype "bidirectional"))
    )
    (net (code "69") (name "unconnected-(U23-FB3M14-Pad19)") (class "Default")
      (node (ref "U23") (pin "19") (pinfunction "FB3M14_19") (pintype "bidirectional"))
    )
    (net (code "70") (name "unconnected-(U23-FB3M15-Pad18)") (class "Default")
      (node (ref "U23") (pin "18") (pinfunction "FB3M15_18") (pintype "bidirectional"))
    )
    (net (code "71") (name "unconnected-(U23-FB4M1-Pad5)") (class "Default")
      (node (ref "U23") (pin "5") (pinfunction "FB4M1_5") (pintype "bidirectional"))
    )
    (net (code "72") (name "unconnected-(U23-FB4M2-Pad6)") (class "Default")
      (node (ref "U23") (pin "6") (pinfunction "FB4M2_6") (pintype "bidirectional"))
    )
    (net (code "73") (name "unconnected-(U23-FB4M11-Pad12)") (class "Default")
      (node (ref "U23") (pin "12") (pinfunction "FB4M11_12") (pintype "bidirectional"))
    )
    (net (code "74") (name "unconnected-(U23-FB4M13-Pad13)") (class "Default")
      (node (ref "U23") (pin "13") (pinfunction "FB4M13_13") (pintype "bidirectional"))
    )
    (net (code "75") (name "unconnected-(U23-FB4M14-Pad14)") (class "Default")
      (node (ref "U23") (pin "14") (pinfunction "FB4M14_14") (pintype "bidirectional"))
    )
    (net (code "76") (name "unconnected-(U23-FB4M15-Pad16)") (class "Default")
      (node (ref "U23") (pin "16") (pinfunction "FB4M15_16") (pintype "bidirectional"))
    )
  )
)
